# wifilights-probe-board.net
KiCad netlist of a schematic drawn in EAGLE
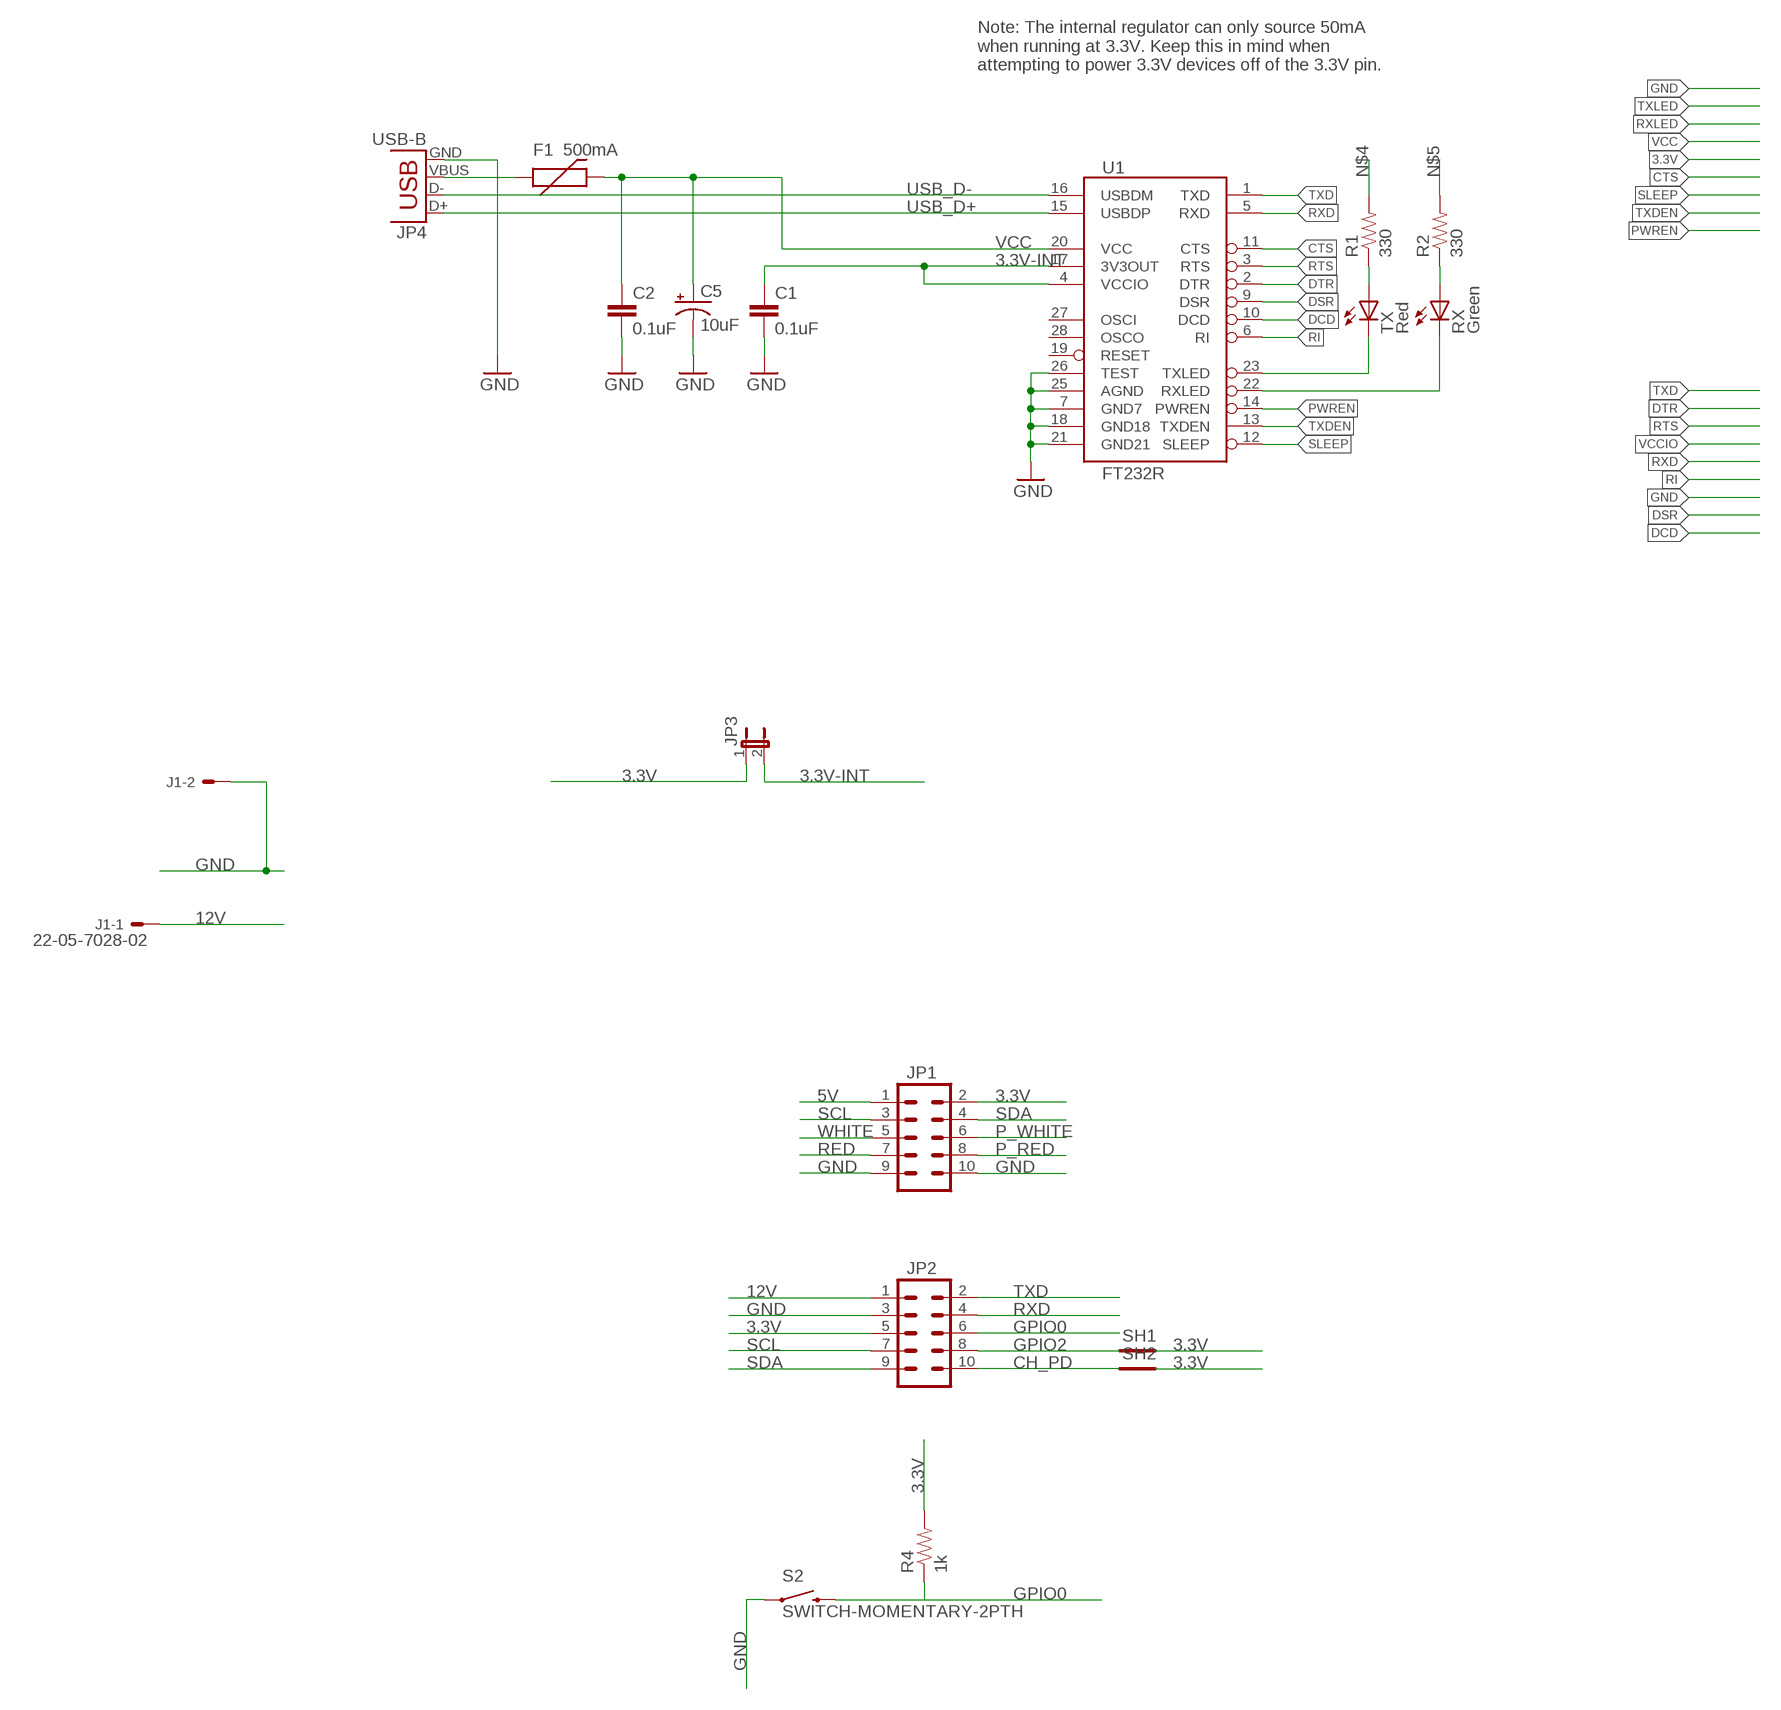
[diagram p0: schematic, sheet 1]

(export (version "E")
  (design (tool "Eeschema 10.0.6"))
  (components
    (comp (ref "C1")
      (value "0.1uF")
      (footprint "eagle-import:0603-CAP")
      (libsource (lib "eagle-import") (part "0.1UF-25V(+80/-20%)(0603)"))
    )
    (comp (ref "C2")
      (value "0.1uF")
      (footprint "eagle-import:0603-CAP")
      (libsource (lib "eagle-import") (part "0.1UF-25V(+80/-20%)(0603)"))
    )
    (comp (ref "C5")
      (value "10uF")
      (footprint "eagle-import:EIA3216")
      (libsource (lib "eagle-import") (part "10UF-16V-10%(TANT)"))
    )
    (comp (ref "F1")
      (value "500mA")
      (footprint "eagle-import:PTC-1206")
      (libsource (lib "eagle-import") (part "PTCSMD"))
    )
    (comp (ref "J1")
      (value "22-05-7028-02")
      (footprint "eagle-import:7395-02")
      (libsource (lib "eagle-import") (part "22-?-0205-7028"))
    )
    (comp (ref "JP1")
      (value "M05X2SHD")
      (footprint "eagle-import:2X5-SHROUDED")
      (libsource (lib "eagle-import") (part "M05X2SHD"))
    )
    (comp (ref "JP2")
      (value "M05X2SHD_LOCK")
      (footprint "eagle-import:2X5-SHROUDED_LOCK")
      (libsource (lib "eagle-import") (part "M05X2SHD_LOCK"))
    )
    (comp (ref "JP3")
      (value "JUMPER-2PTH")
      (footprint "eagle-import:1X02")
      (libsource (lib "eagle-import") (part "JUMPER-2PTH"))
    )
    (comp (ref "JP4")
      (value "USB-B")
      (footprint "eagle-import:USB-B-PTH")
      (libsource (lib "eagle-import") (part "USBPTH"))
    )
    (comp (ref "R1")
      (value "330")
      (footprint "eagle-import:0603-RES")
      (libsource (lib "eagle-import") (part "330OHM1/10W1%(0603)"))
    )
    (comp (ref "R2")
      (value "330")
      (footprint "eagle-import:0603-RES")
      (libsource (lib "eagle-import") (part "330OHM1/10W1%(0603)"))
    )
    (comp (ref "R4")
      (value "1k")
      (footprint "eagle-import:AXIAL-0.3")
      (libsource (lib "eagle-import") (part "RESISTORAXIAL-0.3"))
    )
    (comp (ref "RX")
      (value "Green")
      (footprint "eagle-import:LED-0603")
      (libsource (lib "eagle-import") (part "LED-GREEN0603"))
    )
    (comp (ref "S2")
      (value "SWITCH-MOMENTARY-2PTH")
      (footprint "eagle-import:TACTILE-PTH")
      (libsource (lib "eagle-import") (part "SWITCH-MOMENTARY-2PTH"))
    )
    (comp (ref "SH1")
      (value "SHORT-HT5")
      (footprint "eagle-import:SHORT_TOP-50")
      (libsource (lib "eagle-import") (part "SHORT-HT5"))
    )
    (comp (ref "SH2")
      (value "SHORT-HT5")
      (footprint "eagle-import:SHORT_TOP-50")
      (libsource (lib "eagle-import") (part "SHORT-HT5"))
    )
    (comp (ref "TX")
      (value "Red")
      (footprint "eagle-import:LED-0603")
      (libsource (lib "eagle-import") (part "LED-RED0603"))
    )
    (comp (ref "U1")
      (value "FT232R")
      (footprint "eagle-import:SSOP28DB")
      (libsource (lib "eagle-import") (part "FT232RLSSOP"))
    )
  )
  (nets
    (net (code "1") (name "/3.3V-INT") (class "Default")
      (node (ref "C1") (pin "1") (pinfunction "1_1") (pintype "passive"))
      (node (ref "JP3") (pin "2") (pinfunction "2_2") (pintype "passive"))
      (node (ref "U1") (pin "17") (pinfunction "3V3OUT_17") (pintype "output"))
      (node (ref "U1") (pin "4") (pinfunction "VCCIO_4") (pintype "power_in"))
    )
    (net (code "2") (name "/5V") (class "Default")
      (node (ref "JP1") (pin "1") (pinfunction "1_1") (pintype "passive"))
    )
    (net (code "3") (name "/12V") (class "Default")
      (node (ref "J1") (pin "1") (pinfunction "S_1") (pintype "passive"))
      (node (ref "JP2") (pin "1") (pinfunction "1_1") (pintype "passive"))
    )
    (net (code "4") (name "/CH_PD") (class "Default")
      (node (ref "JP2") (pin "10") (pinfunction "10_10") (pintype "passive"))
      (node (ref "SH2") (pin "1") (pinfunction "P$1_1") (pintype "bidirectional"))
    )
    (net (code "5") (name "/GPIO0") (class "Default")
      (node (ref "JP2") (pin "6") (pinfunction "6_6") (pintype "passive"))
      (node (ref "R4") (pin "P$1") (pinfunction "1_P$1") (pintype "passive"))
      (node (ref "S2") (pin "3") (pinfunction "2_3") (pintype "passive"))
    )
    (net (code "6") (name "/GPIO2") (class "Default")
      (node (ref "JP2") (pin "8") (pinfunction "8_8") (pintype "passive"))
      (node (ref "SH1") (pin "1") (pinfunction "P$1_1") (pintype "bidirectional"))
    )
    (net (code "7") (name "/N$4") (class "Default")
      (node (ref "R1") (pin "2") (pinfunction "2_2") (pintype "passive"))
    )
    (net (code "8") (name "/N$5") (class "Default")
      (node (ref "R2") (pin "2") (pinfunction "2_2") (pintype "passive"))
    )
    (net (code "9") (name "/P_RED") (class "Default")
      (node (ref "JP1") (pin "8") (pinfunction "8_8") (pintype "passive"))
    )
    (net (code "10") (name "/P_WHITE") (class "Default")
      (node (ref "JP1") (pin "6") (pinfunction "6_6") (pintype "passive"))
    )
    (net (code "11") (name "/RED") (class "Default")
      (node (ref "JP1") (pin "7") (pinfunction "7_7") (pintype "passive"))
    )
    (net (code "12") (name "/SCL") (class "Default")
      (node (ref "JP1") (pin "3") (pinfunction "3_3") (pintype "passive"))
      (node (ref "JP2") (pin "7") (pinfunction "7_7") (pintype "passive"))
    )
    (net (code "13") (name "/SDA") (class "Default")
      (node (ref "JP1") (pin "4") (pinfunction "4_4") (pintype "passive"))
      (node (ref "JP2") (pin "9") (pinfunction "9_9") (pintype "passive"))
    )
    (net (code "14") (name "/USB_D+") (class "Default")
      (node (ref "JP4") (pin "D+") (pinfunction "D+_D+") (pintype "bidirectional"))
      (node (ref "U1") (pin "15") (pinfunction "USBDP_15") (pintype "bidirectional"))
    )
    (net (code "15") (name "/USB_D-") (class "Default")
      (node (ref "JP4") (pin "D-") (pinfunction "D-_D-") (pintype "bidirectional"))
      (node (ref "U1") (pin "16") (pinfunction "USBDM_16") (pintype "bidirectional"))
    )
    (net (code "16") (name "/WHITE") (class "Default")
      (node (ref "JP1") (pin "5") (pinfunction "5_5") (pintype "passive"))
    )
    (net (code "17") (name "3.3V") (class "Default")
      (node (ref "JP1") (pin "2") (pinfunction "2_2") (pintype "passive"))
      (node (ref "JP2") (pin "5") (pinfunction "5_5") (pintype "passive"))
      (node (ref "JP3") (pin "1") (pinfunction "1_1") (pintype "passive"))
      (node (ref "R4") (pin "P$2") (pinfunction "2_P$2") (pintype "passive"))
      (node (ref "SH1") (pin "2") (pinfunction "P$2_2") (pintype "bidirectional"))
      (node (ref "SH2") (pin "2") (pinfunction "P$2_2") (pintype "bidirectional"))
    )
    (net (code "18") (name "CTS") (class "Default")
      (node (ref "U1") (pin "11") (pinfunction "CTS_11") (pintype "input"))
    )
    (net (code "19") (name "DCD") (class "Default")
      (node (ref "U1") (pin "10") (pinfunction "DCD_10") (pintype "input"))
    )
    (net (code "20") (name "DSR") (class "Default")
      (node (ref "U1") (pin "9") (pinfunction "DSR_9") (pintype "input"))
    )
    (net (code "21") (name "DTR") (class "Default")
      (node (ref "U1") (pin "2") (pinfunction "DTR_2") (pintype "output"))
    )
    (net (code "22") (name "GND") (class "Default")
      (node (ref "C1") (pin "2") (pinfunction "2_2") (pintype "passive"))
      (node (ref "C2") (pin "2") (pinfunction "2_2") (pintype "passive"))
      (node (ref "C5") (pin "C") (pinfunction "-_C") (pintype "passive"))
      (node (ref "J1") (pin "2") (pinfunction "S_2") (pintype "passive"))
      (node (ref "JP1") (pin "10") (pinfunction "10_10") (pintype "passive"))
      (node (ref "JP1") (pin "9") (pinfunction "9_9") (pintype "passive"))
      (node (ref "JP2") (pin "3") (pinfunction "3_3") (pintype "passive"))
      (node (ref "JP4") (pin "GND") (pinfunction "GND_GND") (pintype "bidirectional"))
      (node (ref "S2") (pin "1") (pinfunction "1_1") (pintype "passive"))
      (node (ref "U1") (pin "18") (pinfunction "GND18_18") (pintype "power_in"))
      (node (ref "U1") (pin "21") (pinfunction "GND21_21") (pintype "power_in"))
      (node (ref "U1") (pin "25") (pinfunction "AGND_25") (pintype "power_in"))
      (node (ref "U1") (pin "26") (pinfunction "TEST_26") (pintype "input"))
      (node (ref "U1") (pin "7") (pinfunction "GND7_7") (pintype "power_in"))
    )
    (net (code "23") (name "Net-(F1-Pad1)") (class "Default")
      (node (ref "F1") (pin "1") (pinfunction "1_1") (pintype "bidirectional"))
      (node (ref "JP4") (pin "VBUS") (pinfunction "VBUS_VBUS") (pintype "bidirectional"))
    )
    (net (code "24") (name "Net-(R1-Pad1)") (class "Default")
      (node (ref "R1") (pin "1") (pinfunction "1_1") (pintype "passive"))
      (node (ref "TX") (pin "A") (pinfunction "A_A") (pintype "passive"))
    )
    (net (code "25") (name "Net-(R2-Pad1)") (class "Default")
      (node (ref "R2") (pin "1") (pinfunction "1_1") (pintype "passive"))
      (node (ref "RX") (pin "A") (pinfunction "A_A") (pintype "passive"))
    )
    (net (code "26") (name "PWREN") (class "Default")
      (node (ref "U1") (pin "14") (pinfunction "PWREN_14") (pintype "input"))
    )
    (net (code "27") (name "RI") (class "Default")
      (node (ref "U1") (pin "6") (pinfunction "RI_6") (pintype "input"))
    )
    (net (code "28") (name "RTS") (class "Default")
      (node (ref "U1") (pin "3") (pinfunction "RTS_3") (pintype "output"))
    )
    (net (code "29") (name "RXD") (class "Default")
      (node (ref "JP2") (pin "4") (pinfunction "4_4") (pintype "passive"))
      (node (ref "U1") (pin "5") (pinfunction "RXD_5") (pintype "input"))
    )
    (net (code "30") (name "RXLED") (class "Default")
      (node (ref "RX") (pin "C") (pinfunction "C_C") (pintype "passive"))
      (node (ref "U1") (pin "22") (pinfunction "RXLED_22") (pintype "input"))
    )
    (net (code "31") (name "SLEEP") (class "Default")
      (node (ref "U1") (pin "12") (pinfunction "SLEEP_12") (pintype "input"))
    )
    (net (code "32") (name "TXD") (class "Default")
      (node (ref "JP2") (pin "2") (pinfunction "2_2") (pintype "passive"))
      (node (ref "U1") (pin "1") (pinfunction "TXD_1") (pintype "output"))
    )
    (net (code "33") (name "TXDEN") (class "Default")
      (node (ref "U1") (pin "13") (pinfunction "TXDEN_13") (pintype "input"))
    )
    (net (code "34") (name "TXLED") (class "Default")
      (node (ref "TX") (pin "C") (pinfunction "C_C") (pintype "passive"))
      (node (ref "U1") (pin "23") (pinfunction "TXLED_23") (pintype "input"))
    )
    (net (code "35") (name "VCC") (class "Default")
      (node (ref "C2") (pin "1") (pinfunction "1_1") (pintype "passive"))
      (node (ref "C5") (pin "A") (pinfunction "+_A") (pintype "passive"))
      (node (ref "F1") (pin "2") (pinfunction "2_2") (pintype "bidirectional"))
      (node (ref "U1") (pin "20") (pinfunction "VCC_20") (pintype "power_in"))
    )
    (net (code "37") (name "unconnected-(U1-OSCI-Pad27)") (class "Default")
      (node (ref "U1") (pin "27") (pinfunction "OSCI_27") (pintype "input"))
    )
    (net (code "38") (name "unconnected-(U1-OSCO-Pad28)") (class "Default")
      (node (ref "U1") (pin "28") (pinfunction "OSCO_28") (pintype "output"))
    )
    (net (code "39") (name "unconnected-(U1-RESET-Pad19)") (class "Default")
      (node (ref "U1") (pin "19") (pinfunction "RESET_19") (pintype "input"))
    )
  )
)
